# micro.net
KiCad netlist of a schematic drawn in Altium Designer
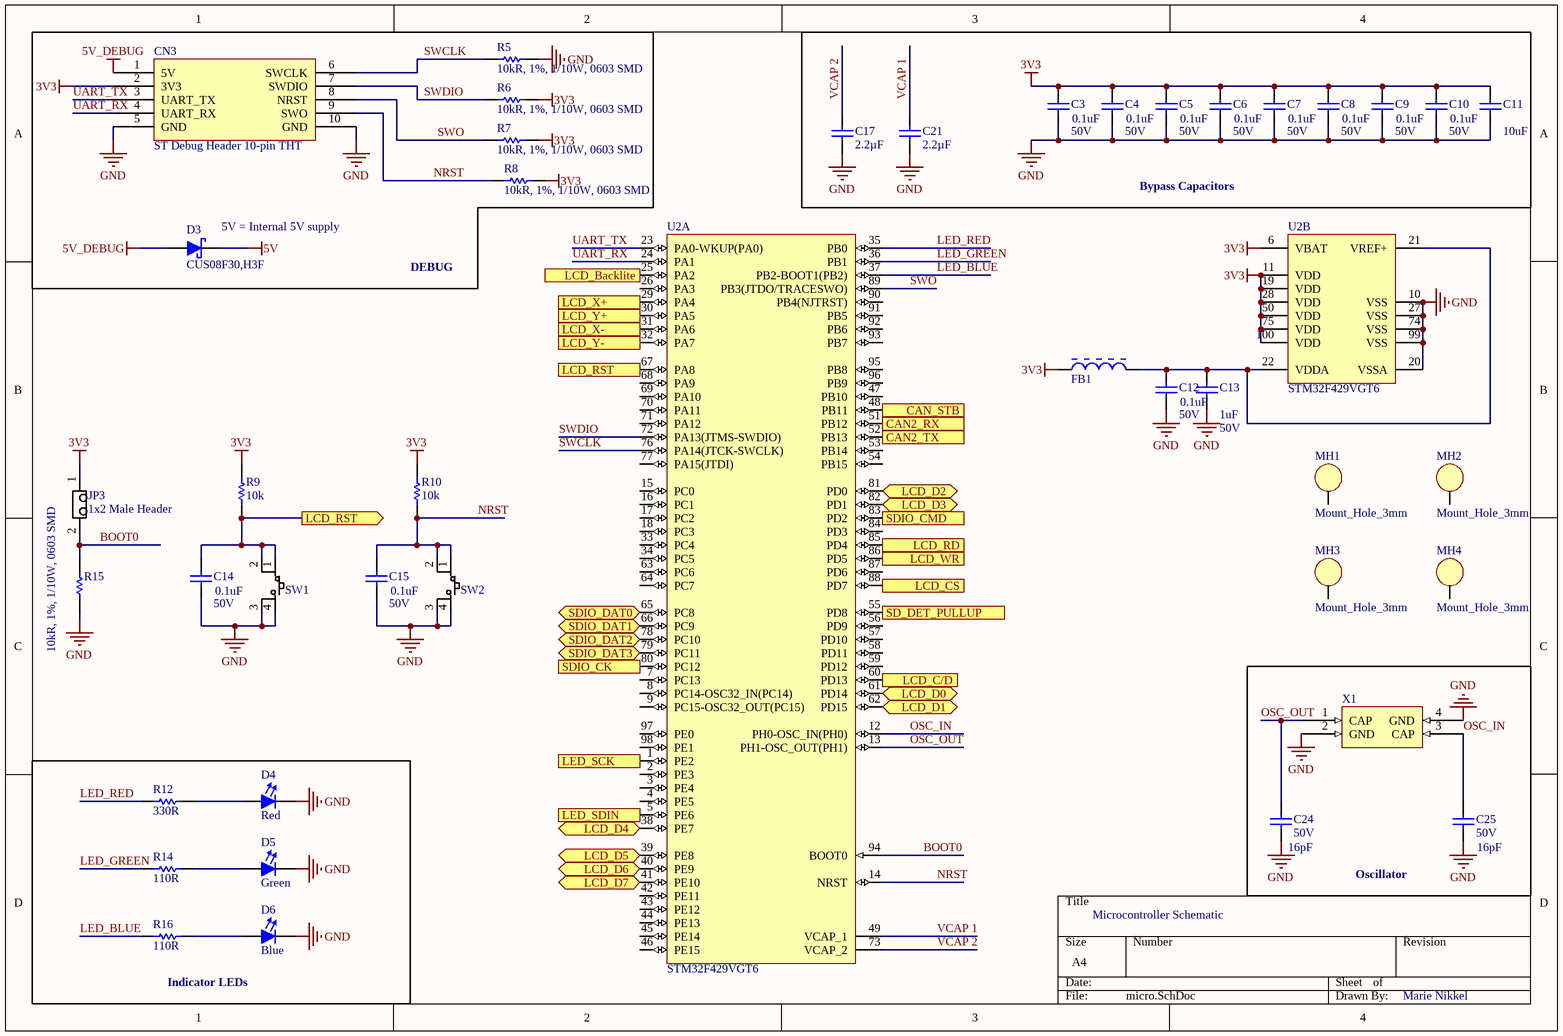
[diagram p0: micro.SchDoc]

(export (version "E")
  (design (tool "Eeschema 10.0.6"))
  (components
    (comp (ref "C3")
      (value "CL10B104JB8NNNC")
      (footprint "FP-CL10-0_1-IPC_A")
      (description "CAP CER 0.1UF 50V X7R 0603")
      (fields
        (field (name "TOLERANCE") "5%")
        (field (name "VOLTAGE") "50V")
        (field (name "CAPACITANCE") "0.1uF")
      )
      (libsource (lib "AUVIC") (part "CAP-NP-2"))
    )
    (comp (ref "C4")
      (value "CL10B104JB8NNNC")
      (footprint "FP-CL10-0_1-IPC_A")
      (description "CAP CER 0.1UF 50V X7R 0603")
      (fields
        (field (name "TOLERANCE") "5%")
        (field (name "VOLTAGE") "50V")
        (field (name "CAPACITANCE") "0.1uF")
      )
      (libsource (lib "AUVIC") (part "CAP-NP-2"))
    )
    (comp (ref "C5")
      (value "CL10B104JB8NNNC")
      (footprint "FP-CL10-0_1-IPC_A")
      (description "CAP CER 0.1UF 50V X7R 0603")
      (fields
        (field (name "TOLERANCE") "5%")
        (field (name "VOLTAGE") "50V")
        (field (name "CAPACITANCE") "0.1uF")
      )
      (libsource (lib "AUVIC") (part "CAP-NP-2"))
    )
    (comp (ref "C6")
      (value "CL10B104JB8NNNC")
      (footprint "FP-CL10-0_1-IPC_A")
      (description "CAP CER 0.1UF 50V X7R 0603")
      (fields
        (field (name "TOLERANCE") "5%")
        (field (name "VOLTAGE") "50V")
        (field (name "CAPACITANCE") "0.1uF")
      )
      (libsource (lib "AUVIC") (part "CAP-NP-2"))
    )
    (comp (ref "C7")
      (value "CL10B104JB8NNNC")
      (footprint "FP-CL10-0_1-IPC_A")
      (description "CAP CER 0.1UF 50V X7R 0603")
      (fields
        (field (name "TOLERANCE") "5%")
        (field (name "VOLTAGE") "50V")
        (field (name "CAPACITANCE") "0.1uF")
      )
      (libsource (lib "AUVIC") (part "CAP-NP-2"))
    )
    (comp (ref "C8")
      (value "CL10B104JB8NNNC")
      (footprint "FP-CL10-0_1-IPC_A")
      (description "CAP CER 0.1UF 50V X7R 0603")
      (fields
        (field (name "TOLERANCE") "5%")
        (field (name "VOLTAGE") "50V")
        (field (name "CAPACITANCE") "0.1uF")
      )
      (libsource (lib "AUVIC") (part "CAP-NP-2"))
    )
    (comp (ref "C9")
      (value "CL10B104JB8NNNC")
      (footprint "FP-CL10-0_1-IPC_A")
      (description "CAP CER 0.1UF 50V X7R 0603")
      (fields
        (field (name "TOLERANCE") "5%")
        (field (name "VOLTAGE") "50V")
        (field (name "CAPACITANCE") "0.1uF")
      )
      (libsource (lib "AUVIC") (part "CAP-NP-2"))
    )
    (comp (ref "C10")
      (value "CL10B104JB8NNNC")
      (footprint "FP-CL10-0_1-IPC_A")
      (description "CAP CER 0.1UF 50V X7R 0603")
      (fields
        (field (name "TOLERANCE") "5%")
        (field (name "VOLTAGE") "50V")
        (field (name "CAPACITANCE") "0.1uF")
      )
      (libsource (lib "AUVIC") (part "CAP-NP-2"))
    )
    (comp (ref "C11")
      (value "CL31B106KBHNNNE")
      (footprint "CAPC3216X180X50ML20T30")
      (description "Cap Ceramic 10uF 50V X7R 10% Pad SMD 1206 125°C T/R")
      (fields (field (name "CAPACITANCE") "10uF") (field (name "TOLERANCE") "10%"))
      (libsource (lib "AUVIC") (part "CAP-NP-2"))
    )
    (comp (ref "C12")
      (value "CL10B104JB8NNNC")
      (footprint "FP-CL10-0_1-IPC_A")
      (description "CAP CER 0.1UF 50V X7R 0603")
      (fields
        (field (name "TOLERANCE") "5%")
        (field (name "VOLTAGE") "50V")
        (field (name "CAPACITANCE") "0.1uF")
      )
      (libsource (lib "AUVIC") (part "CAP-NP-2"))
    )
    (comp (ref "C13")
      (value "CL21B105KBFNNNG")
      (footprint "0803 CAP")
      (description "SAMSUNG ELECTRO-MECHANICS - CL21B105KBFNNNG - MLCC CAPACITORS")
      (fields
        (field (name "TOLERANCE") "10%")
        (field (name "CAPACITANCE") "1uF")
        (field (name "VOLTAGE") "50V")
      )
      (libsource (lib "") (part "Symbol_5"))
    )
    (comp (ref "C14")
      (value "CL10B104JB8NNNC")
      (footprint "FP-CL10-0_1-IPC_A")
      (description "CAP CER 0.1UF 50V X7R 0603")
      (fields
        (field (name "TOLERANCE") "5%")
        (field (name "VOLTAGE") "50V")
        (field (name "CAPACITANCE") "0.1uF")
      )
      (libsource (lib "AUVIC") (part "CAP-NP-2"))
    )
    (comp (ref "C15")
      (value "CL10B104JB8NNNC")
      (footprint "FP-CL10-0_1-IPC_A")
      (description "CAP CER 0.1UF 50V X7R 0603")
      (fields
        (field (name "TOLERANCE") "5%")
        (field (name "VOLTAGE") "50V")
        (field (name "CAPACITANCE") "0.1uF")
      )
      (libsource (lib "AUVIC") (part "CAP-NP-2"))
    )
    (comp (ref "C17")
      (value "2.2µF")
      (footprint "CAPC1608N(0603\")")
      (description "Capacitor, Ceramic, 50V, 10%, 0603 SMD, X5R")
      (fields
        (field (name "Comment") "2.2uF, 50V, 0603 SMD, X5R, Ceramic")
        (field (name "MADE BY") "*")
        (field (name "PUBLISHER") "AUVic")
      )
      (libsource (lib "") (part "Symbol_3"))
    )
    (comp (ref "C21")
      (value "2.2µF")
      (footprint "CAPC1608N(0603\")")
      (description "Capacitor, Ceramic, 50V, 10%, 0603 SMD, X5R")
      (fields
        (field (name "Comment") "2.2uF, 50V, 0603 SMD, X5R, Ceramic")
        (field (name "MADE BY") "*")
        (field (name "PUBLISHER") "AUVic")
      )
      (libsource (lib "") (part "Symbol_3"))
    )
    (comp (ref "C24")
      (value "16pF Ceramic 50V 5% 0603")
      (footprint "CAPC1608X90X35ML10T15")
      (description "Cap Ceramic 16pF 50V C0G 5% SMD 0603 125C Paper T/R")
      (fields
        (field (name "VOLTAGE") "50V")
        (field (name "TOLERANCE") "5%")
        (field (name "CAPACITANCE") "16pF")
      )
      (libsource (lib "AUVIC") (part "CAP"))
    )
    (comp (ref "C25")
      (value "16pF Ceramic 50V 5% 0603")
      (footprint "CAPC1608X90X35ML10T15")
      (description "Cap Ceramic 16pF 50V C0G 5% SMD 0603 125C Paper T/R")
      (fields
        (field (name "VOLTAGE") "50V")
        (field (name "TOLERANCE") "5%")
        (field (name "CAPACITANCE") "16pF")
      )
      (libsource (lib "AUVIC") (part "CAP"))
    )
    (comp (ref "CN3")
      (value "ST Debug Header 10-pin THT")
      (footprint "10-pin shrouded header THT")
      (description "CONN HEADER VERT 10POS 2.54MM")
      (libsource (lib "AUVIC") (part "ST Debug Header 10-pin"))
    )
    (comp (ref "D3")
      (value "CUS08F30,H3F")
      (footprint "SC-76")
      (description "Diode Schottky 30V 800mA Surface Mount USC")
      (libsource (lib "") (part "Symbol_2"))
    )
    (comp (ref "D4")
      (value "LSQ976-NR-1")
      (footprint "FP-LB_Q39E-MFG")
      (description "LED Red 645nm 2-Pin Chip 0603(1608Metric) T/R")
      (fields (field (name "COLOR") "Red"))
      (libsource (lib "AUVIC") (part "Symbol"))
    )
    (comp (ref "D5")
      (value "LT Q39G-Q1OO-25-1")
      (footprint "FP-LB_Q39E-MFG")
      (description "LED GREEN DIFFUSED 0603 SMD")
      (fields (field (name "COLOR") "Green"))
      (libsource (lib "AUVIC") (part "Symbol"))
    )
    (comp (ref "D6")
      (value "LBQ39E-N1OO-35-1")
      (footprint "FP-LB_Q39E-MFG")
      (description "LED BLUE DIFFUSED 0603 SMD")
      (fields (field (name "COLOR") "Blue"))
      (libsource (lib "AUVIC") (part "Symbol"))
    )
    (comp (ref "FB1")
      (value "BLM18AG601SN1D")
      (footprint "MURA-BLM18-F-H1-CHIP-2_V")
      (fields (field (name "TOLERANCE") "25%"))
      (libsource (lib "AUVIC") (part "MURA-FB-2"))
    )
    (comp (ref "JP3")
      (value "1x2 Male Header")
      (footprint "2X1 Males Header")
      (fields (field (name "MADE BY") "Andy Bates"))
      (libsource (lib "AUVIC") (part "1x2 Male Header"))
    )
    (comp (ref "MH1")
      (value "Mount_Hole_3mm")
      (footprint "Mount-Hole_3mm")
      (description "Mounting hold for M3 hex standoff")
      (libsource (lib "AUVIC") (part "Mount_Hole_3mm"))
    )
    (comp (ref "MH2")
      (value "Mount_Hole_3mm")
      (footprint "Mount-Hole_3mm")
      (description "Mounting hold for M3 hex standoff")
      (libsource (lib "AUVIC") (part "Mount_Hole_3mm"))
    )
    (comp (ref "MH3")
      (value "Mount_Hole_3mm")
      (footprint "Mount-Hole_3mm")
      (description "Mounting hold for M3 hex standoff")
      (libsource (lib "AUVIC") (part "Mount_Hole_3mm"))
    )
    (comp (ref "MH4")
      (value "Mount_Hole_3mm")
      (footprint "Mount-Hole_3mm")
      (description "Mounting hold for M3 hex standoff")
      (libsource (lib "AUVIC") (part "Mount_Hole_3mm"))
    )
    (comp (ref "R5")
      (value "10kR, 1%, 1/10W, 0603 SMD")
      (footprint "RESC1608N(0603\")")
      (fields (field (name "MADE BY") "Ashwin Sira"))
      (libsource (lib "") (part "Symbol_1"))
    )
    (comp (ref "R6")
      (value "10kR, 1%, 1/10W, 0603 SMD")
      (footprint "RESC1608N(0603\")")
      (fields (field (name "MADE BY") "Ashwin Sira"))
      (libsource (lib "") (part "Symbol_1"))
    )
    (comp (ref "R7")
      (value "10kR, 1%, 1/10W, 0603 SMD")
      (footprint "RESC1608N(0603\")")
      (fields (field (name "MADE BY") "Ashwin Sira"))
      (libsource (lib "") (part "Symbol_1"))
    )
    (comp (ref "R8")
      (value "10kR, 1%, 1/10W, 0603 SMD")
      (footprint "RESC1608N(0603\")")
      (fields (field (name "MADE BY") "Ashwin Sira"))
      (libsource (lib "") (part "Symbol_1"))
    )
    (comp (ref "R9")
      (value "10k")
      (footprint "RESC1608N(0603\")")
      (description "10kR, 1%, 1/10W, 0603 SMD")
      (fields (field (name "MADE BY") "Ashwin Sira"))
      (libsource (lib "") (part "Symbol_1"))
    )
    (comp (ref "R10")
      (value "10k")
      (footprint "RESC1608N(0603\")")
      (description "10kR, 1%, 1/10W, 0603 SMD")
      (fields (field (name "MADE BY") "Ashwin Sira"))
      (libsource (lib "") (part "Symbol_1"))
    )
    (comp (ref "R12")
      (value "CRCW0603330RFKEA")
      (footprint "FP-CRCW0603-e3-IPC_C")
      (description "Res Thick Film 0603 330 Ohm 1% 0.1W(1/10W) +/-100ppm/ßC Pad SMD Automotive T/R")
      (fields (field (name "TOLERANCE") "1%") (field (name "RESISTANCE") "330R"))
      (libsource (lib "AUVIC") (part "RES"))
    )
    (comp (ref "R14")
      (value "RC0603FR-07110RL")
      (footprint "RESC1608X55X25ML10T15")
      (description "RES SMD 110 OHM 1% 1/10W 0603")
      (fields (field (name "TOLERANCE") "1%") (field (name "RESISTANCE") "110R"))
      (libsource (lib "AUVIC") (part "RES"))
    )
    (comp (ref "R15")
      (value "10kR, 1%, 1/10W, 0603 SMD")
      (footprint "RESC1608N(0603\")")
      (fields (field (name "MADE BY") "Ashwin Sira"))
      (libsource (lib "") (part "Symbol_1"))
    )
    (comp (ref "R16")
      (value "RC0603FR-07110RL")
      (footprint "RESC1608X55X25ML10T15")
      (description "RES SMD 110 OHM 1% 1/10W 0603")
      (fields (field (name "TOLERANCE") "1%") (field (name "RESISTANCE") "110R"))
      (libsource (lib "AUVIC") (part "RES"))
    )
    (comp (ref "SW1")
      (value "PTS645SL43SMTR92LFS")
      (footprint "4-SPST-NO")
      (description "Black Switch Tactile N.O. SPST Round Button Gull Wing 0.05A 12VDC 100000Cycles 1.27N SMD T/R")
      (libsource (lib "") (part "Symbol_4"))
    )
    (comp (ref "SW2")
      (value "PTS645SL43SMTR92LFS")
      (footprint "4-SPST-NO")
      (description "Black Switch Tactile N.O. SPST Round Button Gull Wing 0.05A 12VDC 100000Cycles 1.27N SMD T/R")
      (libsource (lib "") (part "Symbol_4"))
    )
    (comp (ref "U2")
      (value "STM32F429VGT6")
      (footprint "STM-LQFP100_L")
      (description "MCU 32-bit STM32F ARM Cortex M4 RISC 1024KB Flash 2.5V/3.3V 100-Pin LQFP Tray")
      (libsource (lib "AUVIC") (part "MC-ARM-STM32F4X9-SQ100"))
    )
    (comp (ref "X1")
      (value "CRYSTAL 8.0MHZ 16PF SMD")
      (footprint "QFN250P750X520X140_HS-5M")
      (description "8MHz ±30ppm Crystal 16pF 80 Ohms 4-SMD, No Lead")
      (libsource (lib "AUVIC") (part "LFXTAL026380REEL"))
    )
  )
  (nets
    (net (code "1") (name "/BOOT0") (class "Default")
      (node (ref "JP3") (pin "2") (pinfunction "2_2") (pintype "passive"))
      (node (ref "R15") (pin "2") (pinfunction "2_2") (pintype "passive"))
      (node (ref "U2") (pin "94") (pinfunction "BOOT0_94") (pintype "input"))
    )
    (net (code "2") (name "/CAN2_RX") (class "Default")
      (node (ref "U2") (pin "51") (pinfunction "PB12_51") (pintype "bidirectional"))
    )
    (net (code "3") (name "/CAN2_TX") (class "Default")
      (node (ref "U2") (pin "52") (pinfunction "PB13_52") (pintype "bidirectional"))
    )
    (net (code "4") (name "/CAN_STB") (class "Default")
      (node (ref "U2") (pin "48") (pinfunction "PB11_48") (pintype "bidirectional"))
    )
    (net (code "5") (name "/LCD_Backlite") (class "Default")
      (node (ref "U2") (pin "25") (pinfunction "PA2_25") (pintype "bidirectional"))
    )
    (net (code "6") (name "/LCD_CS") (class "Default")
      (node (ref "U2") (pin "88") (pinfunction "PD7_88") (pintype "bidirectional"))
    )
    (net (code "7") (name "/LCD_C{slash}D") (class "Default")
      (node (ref "U2") (pin "60") (pinfunction "PD13_60") (pintype "bidirectional"))
    )
    (net (code "8") (name "/LCD_D0") (class "Default")
      (node (ref "U2") (pin "61") (pinfunction "PD14_61") (pintype "bidirectional"))
    )
    (net (code "9") (name "/LCD_D1") (class "Default")
      (node (ref "U2") (pin "62") (pinfunction "PD15_62") (pintype "bidirectional"))
    )
    (net (code "10") (name "/LCD_D2") (class "Default")
      (node (ref "U2") (pin "81") (pinfunction "PD0_81") (pintype "bidirectional"))
    )
    (net (code "11") (name "/LCD_D3") (class "Default")
      (node (ref "U2") (pin "82") (pinfunction "PD1_82") (pintype "bidirectional"))
    )
    (net (code "12") (name "/LCD_D4") (class "Default")
      (node (ref "U2") (pin "38") (pinfunction "PE7_38") (pintype "bidirectional"))
    )
    (net (code "13") (name "/LCD_D5") (class "Default")
      (node (ref "U2") (pin "39") (pinfunction "PE8_39") (pintype "bidirectional"))
    )
    (net (code "14") (name "/LCD_D6") (class "Default")
      (node (ref "U2") (pin "40") (pinfunction "PE9_40") (pintype "bidirectional"))
    )
    (net (code "15") (name "/LCD_D7") (class "Default")
      (node (ref "U2") (pin "41") (pinfunction "PE10_41") (pintype "bidirectional"))
    )
    (net (code "16") (name "/LCD_RD") (class "Default")
      (node (ref "U2") (pin "85") (pinfunction "PD4_85") (pintype "bidirectional"))
    )
    (net (code "17") (name "/LCD_RST") (class "Default")
      (node (ref "C14") (pin "2") (pinfunction "2_2") (pintype "passive"))
      (node (ref "R9") (pin "1") (pinfunction "1_1") (pintype "passive"))
      (node (ref "SW1") (pin "1") (pinfunction "1_1") (pintype "passive"))
      (node (ref "SW1") (pin "2") (pinfunction "2_2") (pintype "passive"))
      (node (ref "U2") (pin "67") (pinfunction "PA8_67") (pintype "bidirectional"))
    )
    (net (code "18") (name "/LCD_WR") (class "Default")
      (node (ref "U2") (pin "86") (pinfunction "PD5_86") (pintype "bidirectional"))
    )
    (net (code "19") (name "/LCD_X+") (class "Default")
      (node (ref "U2") (pin "29") (pinfunction "PA4_29") (pintype "bidirectional"))
    )
    (net (code "20") (name "/LCD_X-") (class "Default")
      (node (ref "U2") (pin "31") (pinfunction "PA6_31") (pintype "bidirectional"))
    )
    (net (code "21") (name "/LCD_Y+") (class "Default")
      (node (ref "U2") (pin "30") (pinfunction "PA5_30") (pintype "bidirectional"))
    )
    (net (code "22") (name "/LCD_Y-") (class "Default")
      (node (ref "U2") (pin "32") (pinfunction "PA7_32") (pintype "bidirectional"))
    )
    (net (code "23") (name "/LED_BLUE") (class "Default")
      (node (ref "R16") (pin "1") (pinfunction "1_1") (pintype "passive"))
      (node (ref "U2") (pin "37") (pinfunction "PB2-BOOT1(PB2)_37") (pintype "bidirectional"))
    )
    (net (code "24") (name "/LED_GREEN") (class "Default")
      (node (ref "R14") (pin "1") (pinfunction "1_1") (pintype "passive"))
      (node (ref "U2") (pin "36") (pinfunction "PB1_36") (pintype "bidirectional"))
    )
    (net (code "25") (name "/LED_RED") (class "Default")
      (node (ref "R12") (pin "1") (pinfunction "1_1") (pintype "passive"))
      (node (ref "U2") (pin "35") (pinfunction "PB0_35") (pintype "bidirectional"))
    )
    (net (code "26") (name "/LED_SCK") (class "Default")
      (node (ref "U2") (pin "1") (pinfunction "PE2_1") (pintype "bidirectional"))
    )
    (net (code "27") (name "/LED_SDIN") (class "Default")
      (node (ref "U2") (pin "5") (pinfunction "PE6_5") (pintype "bidirectional"))
    )
    (net (code "28") (name "/NRST") (class "Default")
      (node (ref "C15") (pin "2") (pinfunction "2_2") (pintype "passive"))
      (node (ref "CN3") (pin "9") (pinfunction "SWO_9") (pintype "passive"))
      (node (ref "R10") (pin "1") (pinfunction "1_1") (pintype "passive"))
      (node (ref "R8") (pin "1") (pinfunction "1_1") (pintype "passive"))
      (node (ref "SW2") (pin "1") (pinfunction "1_1") (pintype "passive"))
      (node (ref "SW2") (pin "2") (pinfunction "2_2") (pintype "passive"))
      (node (ref "U2") (pin "14") (pinfunction "NRST_14") (pintype "bidirectional"))
    )
    (net (code "29") (name "/OSC_IN") (class "Default")
      (node (ref "C25") (pin "2") (pinfunction "2_2") (pintype "passive"))
      (node (ref "U2") (pin "12") (pinfunction "PH0-OSC_IN(PH0)_12") (pintype "bidirectional"))
      (node (ref "X1") (pin "3") (pinfunction "CAP_3") (pintype "input"))
    )
    (net (code "30") (name "/OSC_OUT") (class "Default")
      (node (ref "C24") (pin "2") (pinfunction "2_2") (pintype "passive"))
      (node (ref "U2") (pin "13") (pinfunction "PH1-OSC_OUT(PH1)_13") (pintype "bidirectional"))
      (node (ref "X1") (pin "1") (pinfunction "CAP_1") (pintype "input"))
    )
    (net (code "31") (name "/SDIO_CK") (class "Default")
      (node (ref "U2") (pin "80") (pinfunction "PC12_80") (pintype "bidirectional"))
    )
    (net (code "32") (name "/SDIO_CMD") (class "Default")
      (node (ref "U2") (pin "83") (pinfunction "PD2_83") (pintype "bidirectional"))
    )
    (net (code "33") (name "/SDIO_DAT0") (class "Default")
      (node (ref "U2") (pin "65") (pinfunction "PC8_65") (pintype "bidirectional"))
    )
    (net (code "34") (name "/SDIO_DAT1") (class "Default")
      (node (ref "U2") (pin "66") (pinfunction "PC9_66") (pintype "bidirectional"))
    )
    (net (code "35") (name "/SDIO_DAT2") (class "Default")
      (node (ref "U2") (pin "78") (pinfunction "PC10_78") (pintype "bidirectional"))
    )
    (net (code "36") (name "/SDIO_DAT3") (class "Default")
      (node (ref "U2") (pin "79") (pinfunction "PC11_79") (pintype "bidirectional"))
    )
    (net (code "37") (name "/SD_DET_PULLUP") (class "Default")
      (node (ref "U2") (pin "55") (pinfunction "PD8_55") (pintype "bidirectional"))
    )
    (net (code "38") (name "/SWCLK") (class "Default")
      (node (ref "CN3") (pin "6") (pinfunction "SWCLK_6") (pintype "passive"))
      (node (ref "R5") (pin "1") (pinfunction "1_1") (pintype "passive"))
      (node (ref "U2") (pin "76") (pinfunction "PA14(JTCK-SWCLK)_76") (pintype "bidirectional"))
    )
    (net (code "39") (name "/SWDIO") (class "Default")
      (node (ref "CN3") (pin "7") (pinfunction "SWDIO_7") (pintype "passive"))
      (node (ref "R6") (pin "1") (pinfunction "1_1") (pintype "passive"))
      (node (ref "U2") (pin "72") (pinfunction "PA13(JTMS-SWDIO)_72") (pintype "bidirectional"))
    )
    (net (code "40") (name "/SWO") (class "Default")
      (node (ref "CN3") (pin "8") (pinfunction "NRST_8") (pintype "passive"))
      (node (ref "R7") (pin "1") (pinfunction "1_1") (pintype "passive"))
      (node (ref "U2") (pin "89") (pinfunction "PB3(JTDO/TRACESWO)_89") (pintype "bidirectional"))
    )
    (net (code "41") (name "/UART_RX") (class "Default")
      (node (ref "CN3") (pin "4") (pinfunction "UART_RX_4") (pintype "passive"))
      (node (ref "U2") (pin "24") (pinfunction "PA1_24") (pintype "bidirectional"))
    )
    (net (code "42") (name "/UART_TX") (class "Default")
      (node (ref "CN3") (pin "3") (pinfunction "UART_TX_3") (pintype "passive"))
      (node (ref "U2") (pin "23") (pinfunction "PA0-WKUP(PA0)_23") (pintype "bidirectional"))
    )
    (net (code "43") (name "/VCAP 1") (class "Default")
      (node (ref "C21") (pin "2") (pinfunction "Cathode_2") (pintype "passive"))
      (node (ref "U2") (pin "49") (pinfunction "VCAP_1_49") (pintype "power_in"))
    )
    (net (code "44") (name "/VCAP 2") (class "Default")
      (node (ref "C17") (pin "2") (pinfunction "Cathode_2") (pintype "passive"))
      (node (ref "U2") (pin "73") (pinfunction "VCAP_2_73") (pintype "power_in"))
    )
    (net (code "45") (name "3V3") (class "Default")
      (node (ref "C10") (pin "2") (pinfunction "2_2") (pintype "passive"))
      (node (ref "C11") (pin "2") (pinfunction "2_2") (pintype "passive"))
      (node (ref "C3") (pin "2") (pinfunction "2_2") (pintype "passive"))
      (node (ref "C4") (pin "2") (pinfunction "2_2") (pintype "passive"))
      (node (ref "C5") (pin "2") (pinfunction "2_2") (pintype "passive"))
      (node (ref "C6") (pin "2") (pinfunction "2_2") (pintype "passive"))
      (node (ref "C7") (pin "2") (pinfunction "2_2") (pintype "passive"))
      (node (ref "C8") (pin "2") (pinfunction "2_2") (pintype "passive"))
      (node (ref "C9") (pin "2") (pinfunction "2_2") (pintype "passive"))
      (node (ref "CN3") (pin "2") (pinfunction "3V3_2") (pintype "passive"))
      (node (ref "FB1") (pin "1") (pinfunction "1_1") (pintype "passive"))
      (node (ref "JP3") (pin "1") (pinfunction "1_1") (pintype "passive"))
      (node (ref "R10") (pin "2") (pinfunction "2_2") (pintype "passive"))
      (node (ref "R6") (pin "2") (pinfunction "2_2") (pintype "passive"))
      (node (ref "R7") (pin "2") (pinfunction "2_2") (pintype "passive"))
      (node (ref "R8") (pin "2") (pinfunction "2_2") (pintype "passive"))
      (node (ref "R9") (pin "2") (pinfunction "2_2") (pintype "passive"))
      (node (ref "U2") (pin "100") (pinfunction "VDD_100") (pintype "power_in"))
      (node (ref "U2") (pin "11") (pinfunction "VDD_11") (pintype "power_in"))
      (node (ref "U2") (pin "19") (pinfunction "VDD_19") (pintype "power_in"))
      (node (ref "U2") (pin "28") (pinfunction "VDD_28") (pintype "power_in"))
      (node (ref "U2") (pin "50") (pinfunction "VDD_50") (pintype "power_in"))
      (node (ref "U2") (pin "6") (pinfunction "VBAT_6") (pintype "power_in"))
      (node (ref "U2") (pin "75") (pinfunction "VDD_75") (pintype "power_in"))
    )
    (net (code "46") (name "5V") (class "Default")
      (node (ref "D3") (pin "K") (pinfunction "Cathode_K") (pintype "passive"))
    )
    (net (code "47") (name "5V_DEBUG") (class "Default")
      (node (ref "CN3") (pin "1") (pinfunction "5V_1") (pintype "passive"))
      (node (ref "D3") (pin "A") (pinfunction "Anode_A") (pintype "passive"))
    )
    (net (code "48") (name "GND") (class "Default")
      (node (ref "C10") (pin "1") (pinfunction "1_1") (pintype "passive"))
      (node (ref "C11") (pin "1") (pinfunction "1_1") (pintype "passive"))
      (node (ref "C12") (pin "1") (pinfunction "1_1") (pintype "passive"))
      (node (ref "C13") (pin "1") (pinfunction "1_1") (pintype "passive"))
      (node (ref "C14") (pin "1") (pinfunction "1_1") (pintype "passive"))
      (node (ref "C15") (pin "1") (pinfunction "1_1") (pintype "passive"))
      (node (ref "C17") (pin "1") (pinfunction "Anode_1") (pintype "passive"))
      (node (ref "C21") (pin "1") (pinfunction "Anode_1") (pintype "passive"))
      (node (ref "C24") (pin "1") (pinfunction "1_1") (pintype "passive"))
      (node (ref "C25") (pin "1") (pinfunction "1_1") (pintype "passive"))
      (node (ref "C3") (pin "1") (pinfunction "1_1") (pintype "passive"))
      (node (ref "C4") (pin "1") (pinfunction "1_1") (pintype "passive"))
      (node (ref "C5") (pin "1") (pinfunction "1_1") (pintype "passive"))
      (node (ref "C6") (pin "1") (pinfunction "1_1") (pintype "passive"))
      (node (ref "C7") (pin "1") (pinfunction "1_1") (pintype "passive"))
      (node (ref "C8") (pin "1") (pinfunction "1_1") (pintype "passive"))
      (node (ref "C9") (pin "1") (pinfunction "1_1") (pintype "passive"))
      (node (ref "CN3") (pin "10") (pinfunction "GND_10") (pintype "passive"))
      (node (ref "CN3") (pin "5") (pinfunction "GND_5") (pintype "passive"))
      (node (ref "D4") (pin "1") (pinfunction "Cathode_1") (pintype "passive"))
      (node (ref "D5") (pin "1") (pinfunction "Cathode_1") (pintype "passive"))
      (node (ref "D6") (pin "1") (pinfunction "Cathode_1") (pintype "passive"))
      (node (ref "R15") (pin "1") (pinfunction "1_1") (pintype "passive"))
      (node (ref "R5") (pin "2") (pinfunction "2_2") (pintype "passive"))
      (node (ref "SW1") (pin "3") (pinfunction "3_3") (pintype "passive"))
      (node (ref "SW1") (pin "4") (pinfunction "4_4") (pintype "passive"))
      (node (ref "SW2") (pin "3") (pinfunction "3_3") (pintype "passive"))
      (node (ref "SW2") (pin "4") (pinfunction "4_4") (pintype "passive"))
      (node (ref "U2") (pin "10") (pinfunction "VSS_10") (pintype "power_in"))
      (node (ref "U2") (pin "20") (pinfunction "VSSA_20") (pintype "power_in"))
      (node (ref "U2") (pin "27") (pinfunction "VSS_27") (pintype "power_in"))
      (node (ref "U2") (pin "74") (pinfunction "VSS_74") (pintype "power_in"))
      (node (ref "U2") (pin "99") (pinfunction "VSS_99") (pintype "power_in"))
      (node (ref "X1") (pin "2") (pinfunction "GND_2") (pintype "input"))
      (node (ref "X1") (pin "4") (pinfunction "GND_4") (pintype "input"))
    )
    (net (code "49") (name "Net-(D4-Anode)") (class "Default")
      (node (ref "D4") (pin "2") (pinfunction "Anode_2") (pintype "passive"))
      (node (ref "R12") (pin "2") (pinfunction "2_2") (pintype "passive"))
    )
    (net (code "50") (name "Net-(D5-Anode)") (class "Default")
      (node (ref "D5") (pin "2") (pinfunction "Anode_2") (pintype "passive"))
      (node (ref "R14") (pin "2") (pinfunction "2_2") (pintype "passive"))
    )
    (net (code "51") (name "Net-(D6-Anode)") (class "Default")
      (node (ref "D6") (pin "2") (pinfunction "Anode_2") (pintype "passive"))
      (node (ref "R16") (pin "2") (pinfunction "2_2") (pintype "passive"))
    )
    (net (code "52") (name "Net-(U2B-VDDA)") (class "Default")
      (node (ref "C12") (pin "2") (pinfunction "2_2") (pintype "passive"))
      (node (ref "C13") (pin "2") (pinfunction "2_2") (pintype "passive"))
      (node (ref "FB1") (pin "2") (pinfunction "2_2") (pintype "passive"))
      (node (ref "U2") (pin "21") (pinfunction "VREF+_21") (pintype "power_in"))
      (node (ref "U2") (pin "22") (pinfunction "VDDA_22") (pintype "power_in"))
    )
    (net (code "53") (name "unconnected-(MH1-Pad1)") (class "Default")
      (node (ref "MH1") (pin "1") (pinfunction "1_1") (pintype "passive"))
    )
    (net (code "54") (name "unconnected-(MH2-Pad1)") (class "Default")
      (node (ref "MH2") (pin "1") (pinfunction "1_1") (pintype "passive"))
    )
    (net (code "55") (name "unconnected-(MH3-Pad1)") (class "Default")
      (node (ref "MH3") (pin "1") (pinfunction "1_1") (pintype "passive"))
    )
    (net (code "56") (name "unconnected-(MH4-Pad1)") (class "Default")
      (node (ref "MH4") (pin "1") (pinfunction "1_1") (pintype "passive"))
    )
    (net (code "57") (name "unconnected-(U2A-PA3-Pad26)") (class "Default")
      (node (ref "U2") (pin "26") (pinfunction "PA3_26") (pintype "bidirectional"))
    )
    (net (code "58") (name "unconnected-(U2A-PA9-Pad68)") (class "Default")
      (node (ref "U2") (pin "68") (pinfunction "PA9_68") (pintype "bidirectional"))
    )
    (net (code "59") (name "unconnected-(U2A-PA10-Pad69)") (class "Default")
      (node (ref "U2") (pin "69") (pinfunction "PA10_69") (pintype "bidirectional"))
    )
    (net (code "60") (name "unconnected-(U2A-PA11-Pad70)") (class "Default")
      (node (ref "U2") (pin "70") (pinfunction "PA11_70") (pintype "bidirectional"))
    )
    (net (code "61") (name "unconnected-(U2A-PA12-Pad71)") (class "Default")
      (node (ref "U2") (pin "71") (pinfunction "PA12_71") (pintype "bidirectional"))
    )
    (net (code "62") (name "unconnected-(U2A-PA15(JTDI)-Pad77)") (class "Default")
      (node (ref "U2") (pin "77") (pinfunction "PA15(JTDI)_77") (pintype "bidirectional"))
    )
    (net (code "63") (name "unconnected-(U2A-PB4(NJTRST)-Pad90)") (class "Default")
      (node (ref "U2") (pin "90") (pinfunction "PB4(NJTRST)_90") (pintype "bidirectional"))
    )
    (net (code "64") (name "unconnected-(U2A-PB5-Pad91)") (class "Default")
      (node (ref "U2") (pin "91") (pinfunction "PB5_91") (pintype "bidirectional"))
    )
    (net (code "65") (name "unconnected-(U2A-PB6-Pad92)") (class "Default")
      (node (ref "U2") (pin "92") (pinfunction "PB6_92") (pintype "bidirectional"))
    )
    (net (code "66") (name "unconnected-(U2A-PB7-Pad93)") (class "Default")
      (node (ref "U2") (pin "93") (pinfunction "PB7_93") (pintype "bidirectional"))
    )
    (net (code "67") (name "unconnected-(U2A-PB8-Pad95)") (class "Default")
      (node (ref "U2") (pin "95") (pinfunction "PB8_95") (pintype "bidirectional"))
    )
    (net (code "68") (name "unconnected-(U2A-PB9-Pad96)") (class "Default")
      (node (ref "U2") (pin "96") (pinfunction "PB9_96") (pintype "bidirectional"))
    )
    (net (code "69") (name "unconnected-(U2A-PB10-Pad47)") (class "Default")
      (node (ref "U2") (pin "47") (pinfunction "PB10_47") (pintype "bidirectional"))
    )
    (net (code "70") (name "unconnected-(U2A-PB14-Pad53)") (class "Default")
      (node (ref "U2") (pin "53") (pinfunction "PB14_53") (pintype "bidirectional"))
    )
    (net (code "71") (name "unconnected-(U2A-PB15-Pad54)") (class "Default")
      (node (ref "U2") (pin "54") (pinfunction "PB15_54") (pintype "bidirectional"))
    )
    (net (code "72") (name "unconnected-(U2A-PC0-Pad15)") (class "Default")
      (node (ref "U2") (pin "15") (pinfunction "PC0_15") (pintype "bidirectional"))
    )
    (net (code "73") (name "unconnected-(U2A-PC1-Pad16)") (class "Default")
      (node (ref "U2") (pin "16") (pinfunction "PC1_16") (pintype "bidirectional"))
    )
    (net (code "74") (name "unconnected-(U2A-PC2-Pad17)") (class "Default")
      (node (ref "U2") (pin "17") (pinfunction "PC2_17") (pintype "bidirectional"))
    )
    (net (code "75") (name "unconnected-(U2A-PC3-Pad18)") (class "Default")
      (node (ref "U2") (pin "18") (pinfunction "PC3_18") (pintype "bidirectional"))
    )
    (net (code "76") (name "unconnected-(U2A-PC4-Pad33)") (class "Default")
      (node (ref "U2") (pin "33") (pinfunction "PC4_33") (pintype "bidirectional"))
    )
    (net (code "77") (name "unconnected-(U2A-PC5-Pad34)") (class "Default")
      (node (ref "U2") (pin "34") (pinfunction "PC5_34") (pintype "bidirectional"))
    )
    (net (code "78") (name "unconnected-(U2A-PC6-Pad63)") (class "Default")
      (node (ref "U2") (pin "63") (pinfunction "PC6_63") (pintype "bidirectional"))
    )
    (net (code "79") (name "unconnected-(U2A-PC7-Pad64)") (class "Default")
      (node (ref "U2") (pin "64") (pinfunction "PC7_64") (pintype "bidirectional"))
    )
    (net (code "80") (name "unconnected-(U2A-PC13-Pad7)") (class "Default")
      (node (ref "U2") (pin "7") (pinfunction "PC13_7") (pintype "bidirectional"))
    )
    (net (code "81") (name "unconnected-(U2A-PC14-OSC32_IN(PC14)-Pad8)") (class "Default")
      (node (ref "U2") (pin "8") (pinfunction "PC14-OSC32_IN(PC14)_8") (pintype "bidirectional"))
    )
    (net (code "82") (name "unconnected-(U2A-PC15-OSC32_OUT(PC15)-Pad9)") (class "Default")
      (node (ref "U2") (pin "9") (pinfunction "PC15-OSC32_OUT(PC15)_9") (pintype "bidirectional"))
    )
    (net (code "83") (name "unconnected-(U2A-PD3-Pad84)") (class "Default")
      (node (ref "U2") (pin "84") (pinfunction "PD3_84") (pintype "bidirectional"))
    )
    (net (code "84") (name "unconnected-(U2A-PD6-Pad87)") (class "Default")
      (node (ref "U2") (pin "87") (pinfunction "PD6_87") (pintype "bidirectional"))
    )
    (net (code "85") (name "unconnected-(U2A-PD9-Pad56)") (class "Default")
      (node (ref "U2") (pin "56") (pinfunction "PD9_56") (pintype "bidirectional"))
    )
    (net (code "86") (name "unconnected-(U2A-PD10-Pad57)") (class "Default")
      (node (ref "U2") (pin "57") (pinfunction "PD10_57") (pintype "bidirectional"))
    )
    (net (code "87") (name "unconnected-(U2A-PD11-Pad58)") (class "Default")
      (node (ref "U2") (pin "58") (pinfunction "PD11_58") (pintype "bidirectional"))
    )
    (net (code "88") (name "unconnected-(U2A-PD12-Pad59)") (class "Default")
      (node (ref "U2") (pin "59") (pinfunction "PD12_59") (pintype "bidirectional"))
    )
    (net (code "89") (name "unconnected-(U2A-PE0-Pad97)") (class "Default")
      (node (ref "U2") (pin "97") (pinfunction "PE0_97") (pintype "bidirectional"))
    )
    (net (code "90") (name "unconnected-(U2A-PE1-Pad98)") (class "Default")
      (node (ref "U2") (pin "98") (pinfunction "PE1_98") (pintype "bidirectional"))
    )
    (net (code "91") (name "unconnected-(U2A-PE3-Pad2)") (class "Default")
      (node (ref "U2") (pin "2") (pinfunction "PE3_2") (pintype "bidirectional"))
    )
    (net (code "92") (name "unconnected-(U2A-PE4-Pad3)") (class "Default")
      (node (ref "U2") (pin "3") (pinfunction "PE4_3") (pintype "bidirectional"))
    )
    (net (code "93") (name "unconnected-(U2A-PE5-Pad4)") (class "Default")
      (node (ref "U2") (pin "4") (pinfunction "PE5_4") (pintype "bidirectional"))
    )
    (net (code "94") (name "unconnected-(U2A-PE11-Pad42)") (class "Default")
      (node (ref "U2") (pin "42") (pinfunction "PE11_42") (pintype "bidirectional"))
    )
    (net (code "95") (name "unconnected-(U2A-PE12-Pad43)") (class "Default")
      (node (ref "U2") (pin "43") (pinfunction "PE12_43") (pintype "bidirectional"))
    )
    (net (code "96") (name "unconnected-(U2A-PE13-Pad44)") (class "Default")
      (node (ref "U2") (pin "44") (pinfunction "PE13_44") (pintype "bidirectional"))
    )
    (net (code "97") (name "unconnected-(U2A-PE14-Pad45)") (class "Default")
      (node (ref "U2") (pin "45") (pinfunction "PE14_45") (pintype "bidirectional"))
    )
    (net (code "98") (name "unconnected-(U2A-PE15-Pad46)") (class "Default")
      (node (ref "U2") (pin "46") (pinfunction "PE15_46") (pintype "bidirectional"))
    )
  )
)
